# Reed_Switch_Vertical_v1_0.net
KiCad netlist of a schematic drawn in Altium Designer
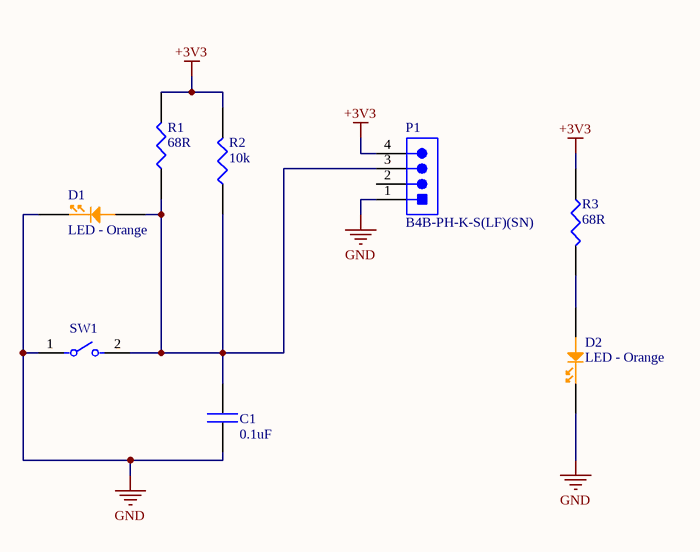
[diagram p0: Reed_Switch_Vertical_v1.0.SchDoc]

(export (version "E")
  (design (tool "Eeschema 10.0.6"))
  (components
    (comp (ref "C1")
      (value "0.1uF")
      (footprint "0.1uF 0603")
      (description "CAP CER 0.1UF 16V X7R 0603")
      (fields
        (field (name "MANUFACTURER") "KEMET")
        (field (name "MANUFACTURER PART NUMBER") "C0603C104M4RACTU")
      )
      (libsource (lib "Limit_Switch") (part "C0603C104M4RACTU"))
    )
    (comp (ref "D1")
      (value "LED - Orange")
      (footprint "LED0603-Orange")
      (description "LED ORANGE CLEAR SMD")
      (fields
        (field (name "MANUFACTURER") "Vishay Lite-On")
        (field (name "MANUFACTURER PART NUMBER") "LTST-C191KFKT")
      )
      (libsource (lib "Limit_Switch") (part "LTST-C191KFKT"))
    )
    (comp (ref "D2")
      (value "LED - Orange")
      (footprint "LED0603-Orange")
      (description "LED ORANGE CLEAR SMD")
      (fields
        (field (name "MANUFACTURER") "Vishay Lite-On")
        (field (name "MANUFACTURER PART NUMBER") "LTST-C191KFKT")
      )
      (libsource (lib "Limit_Switch") (part "LTST-C191KFKT"))
    )
    (comp (ref "P1")
      (value "B4B-PH-K-S(LF)(SN)")
      (footprint "JST-B4B-PH-K-S_V")
      (fields (field (name "MANUFACTURER") "JST"))
      (libsource (lib "Altium Content Vault") (part "CN-1P-M-R4"))
    )
    (comp (ref "R1")
      (value "68R")
      (footprint "68R 0603")
      (description "CRGP 0603 68R 1%")
      (fields
        (field (name "MANUFACTURER") "TE Connectivity")
        (field (name "MANUFACTURER PART NUMBER") "CRGP0603F68R")
      )
      (libsource (lib "Limit_Switch") (part "CRGP0603F68R"))
    )
    (comp (ref "R2")
      (value "10k")
      (footprint "10k R0603")
      (description "RES 10.0K OHM 1/10W 1% 0603")
      (fields
        (field (name "MANUFACTURER") "TE Connectivity")
        (field (name "MANUFACTURER PART NUMBER") "CRG0603F10K/10")
      )
      (libsource (lib "Limit_Switch") (part "CRG0603F10K/10"))
    )
    (comp (ref "R3")
      (value "68R")
      (footprint "68R 0603")
      (description "CRGP 0603 68R 1%")
      (fields
        (field (name "MANUFACTURER") "TE Connectivity")
        (field (name "MANUFACTURER PART NUMBER") "CRGP0603F68R")
      )
      (libsource (lib "Limit_Switch") (part "CRGP0603F68R"))
    )
    (comp (ref "SW1")
      (value "MDSR-4-12-23")
      (footprint "Littelfuse_MDSR-4_MFG")
      (libsource (lib "Switch_Littelfuse_MDSR-4-12-23_eec") (part "MDSR-4-12-23"))
    )
  )
  (nets
    (net (code "1") (name "+3V3") (class "Default")
      (node (ref "P1") (pin "4") (pinfunction "4_4") (pintype "passive"))
      (node (ref "R1") (pin "2") (pinfunction "2_2") (pintype "passive"))
      (node (ref "R2") (pin "2") (pinfunction "2_2") (pintype "passive"))
      (node (ref "R3") (pin "1") (pinfunction "1_1") (pintype "passive"))
    )
    (net (code "2") (name "GND") (class "Default")
      (node (ref "C1") (pin "1") (pinfunction "1_1") (pintype "passive"))
      (node (ref "D1") (pin "1") (pinfunction "Cathode_1") (pintype "passive"))
      (node (ref "D2") (pin "1") (pinfunction "Cathode_1") (pintype "passive"))
      (node (ref "P1") (pin "1") (pinfunction "1_1") (pintype "passive"))
      (node (ref "SW1") (pin "1") (pinfunction "1_1") (pintype "passive"))
    )
    (net (code "3") (name "Net-(D1-Anode)") (class "Default")
      (node (ref "C1") (pin "2") (pinfunction "2_2") (pintype "passive"))
      (node (ref "D1") (pin "2") (pinfunction "Anode_2") (pintype "passive"))
      (node (ref "P1") (pin "3") (pinfunction "3_3") (pintype "passive"))
      (node (ref "R1") (pin "1") (pinfunction "1_1") (pintype "passive"))
      (node (ref "R2") (pin "1") (pinfunction "1_1") (pintype "passive"))
      (node (ref "SW1") (pin "2") (pinfunction "2_2") (pintype "passive"))
    )
    (net (code "4") (name "Net-(D2-Anode)") (class "Default")
      (node (ref "D2") (pin "2") (pinfunction "Anode_2") (pintype "passive"))
      (node (ref "R3") (pin "2") (pinfunction "2_2") (pintype "passive"))
    )
    (net (code "5") (name "unconnected-(P1-Pad2)") (class "Default")
      (node (ref "P1") (pin "2") (pinfunction "2_2") (pintype "passive"))
    )
  )
)
